# Qwiic_Shield_for_Photon.net
KiCad netlist of a schematic drawn in EAGLE
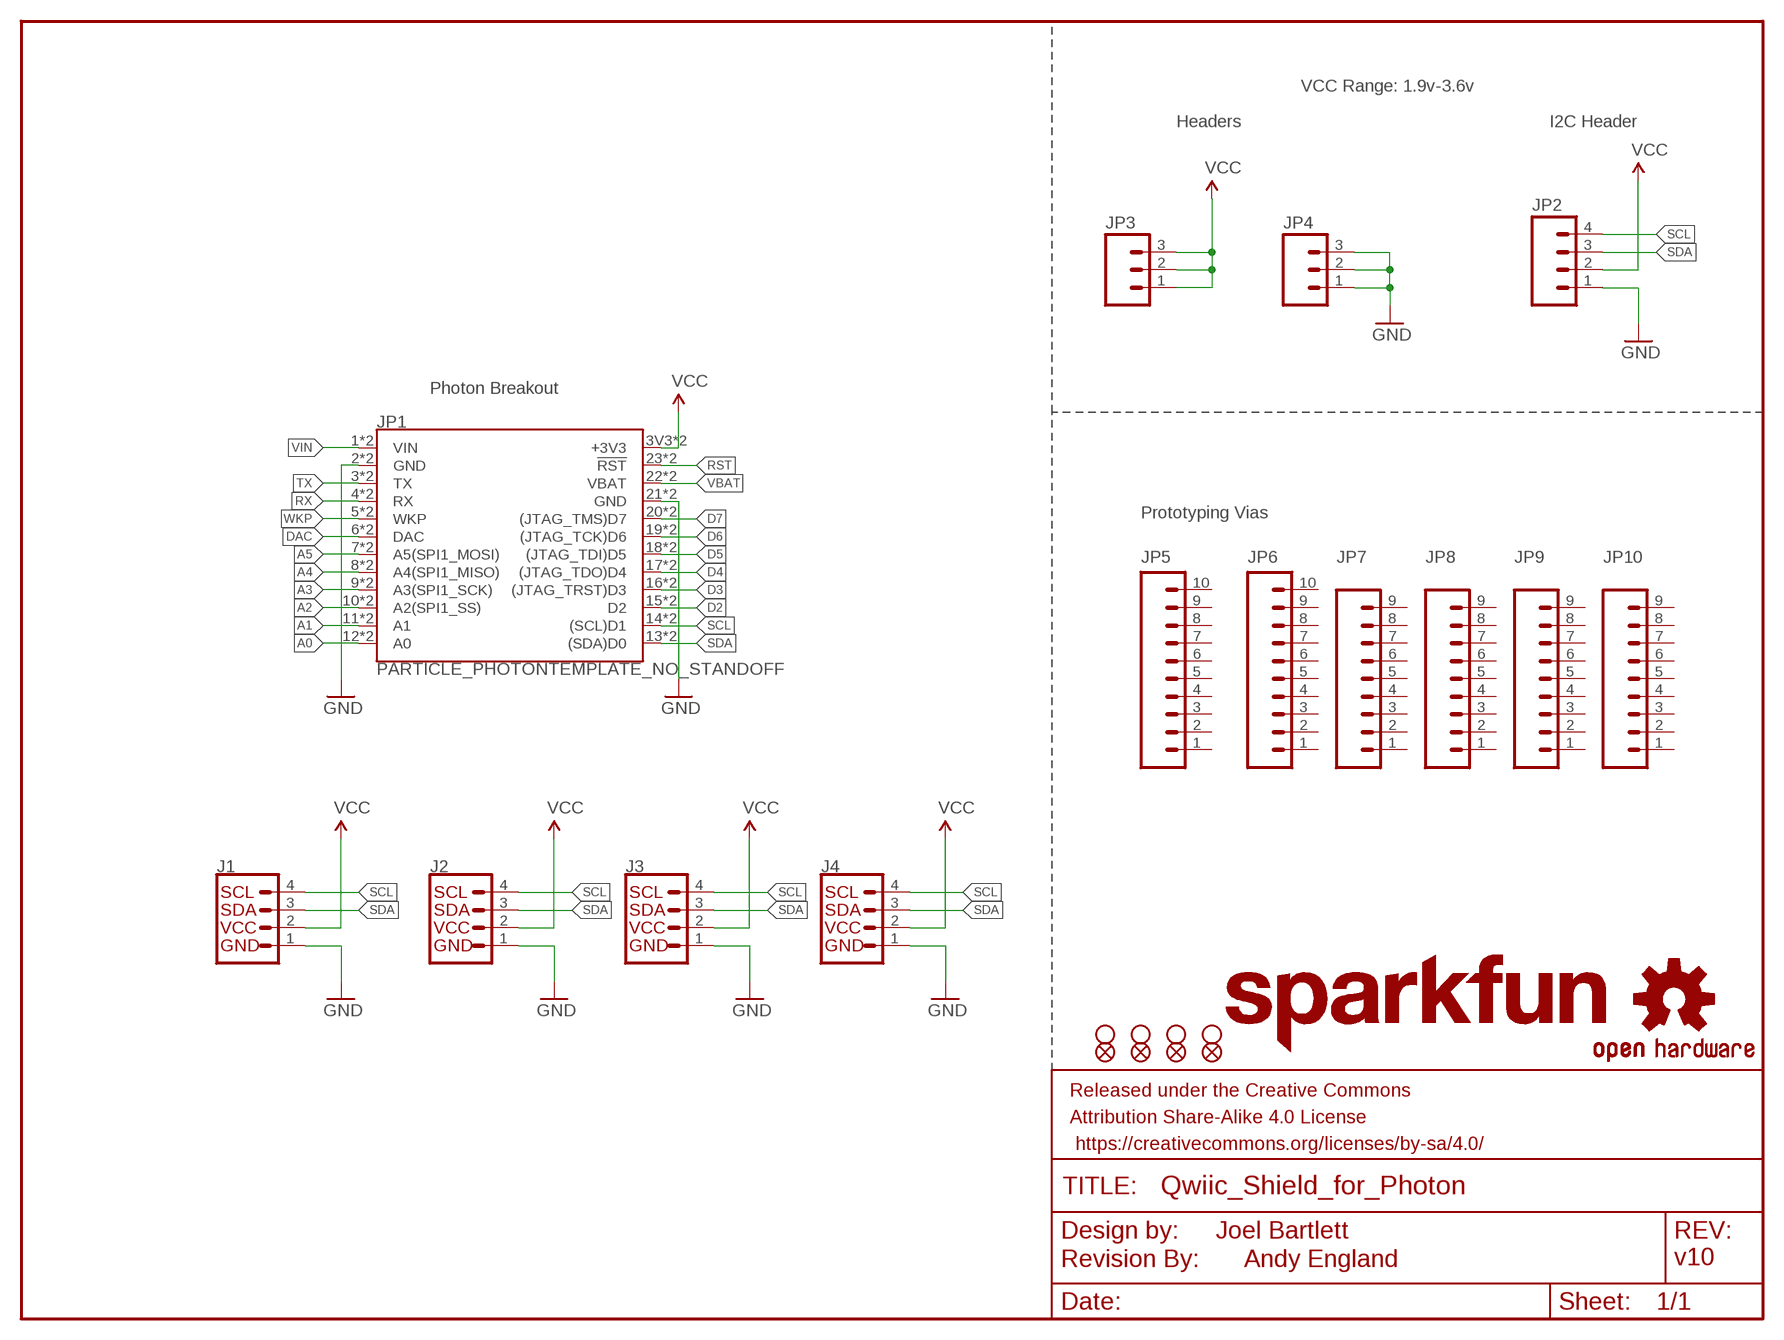
[diagram p0: schematic, sheet 1]

(export (version "E")
  (design (tool "Eeschema 10.0.6"))
  (components
    (comp (ref "FD1")
      (value "FIDUCIALUFIDUCIAL")
      (footprint "eagle-import:FIDUCIAL-MICRO")
      (libsource (lib "eagle-import") (part "FIDUCIALUFIDUCIAL"))
    )
    (comp (ref "FD2")
      (value "FIDUCIALUFIDUCIAL")
      (footprint "eagle-import:FIDUCIAL-MICRO")
      (libsource (lib "eagle-import") (part "FIDUCIALUFIDUCIAL"))
    )
    (comp (ref "FD3")
      (value "FIDUCIALUFIDUCIAL")
      (footprint "eagle-import:FIDUCIAL-MICRO")
      (libsource (lib "eagle-import") (part "FIDUCIALUFIDUCIAL"))
    )
    (comp (ref "FD4")
      (value "FIDUCIALUFIDUCIAL")
      (footprint "eagle-import:FIDUCIAL-MICRO")
      (libsource (lib "eagle-import") (part "FIDUCIALUFIDUCIAL"))
    )
    (comp (ref "FRAME1")
      (value "FRAME-LETTER")
      (footprint "eagle-import:CREATIVE_COMMONS")
      (libsource (lib "eagle-import") (part "FRAME-LETTER"))
    )
    (comp (ref "H1")
      (value "STAND-OFF")
      (footprint "eagle-import:STAND-OFF")
      (libsource (lib "eagle-import") (part "STAND-OFF"))
    )
    (comp (ref "H2")
      (value "STAND-OFF")
      (footprint "eagle-import:STAND-OFF")
      (libsource (lib "eagle-import") (part "STAND-OFF"))
    )
    (comp (ref "H3")
      (value "STAND-OFF")
      (footprint "eagle-import:STAND-OFF")
      (libsource (lib "eagle-import") (part "STAND-OFF"))
    )
    (comp (ref "H4")
      (value "STAND-OFF")
      (footprint "eagle-import:STAND-OFF")
      (libsource (lib "eagle-import") (part "STAND-OFF"))
    )
    (comp (ref "J1")
      (value "QWIIC_CONNECTORJS-1MM")
      (footprint "eagle-import:1X04_1MM_RA")
      (libsource (lib "eagle-import") (part "QWIIC_CONNECTORJS-1MM"))
    )
    (comp (ref "J2")
      (value "QWIIC_CONNECTORJS-1MM")
      (footprint "eagle-import:1X04_1MM_RA")
      (libsource (lib "eagle-import") (part "QWIIC_CONNECTORJS-1MM"))
    )
    (comp (ref "J3")
      (value "QWIIC_CONNECTORJS-1MM")
      (footprint "eagle-import:1X04_1MM_RA")
      (libsource (lib "eagle-import") (part "QWIIC_CONNECTORJS-1MM"))
    )
    (comp (ref "J4")
      (value "I2C_STANDARDJS-1MM")
      (footprint "eagle-import:1X04_1MM_RA")
      (libsource (lib "eagle-import") (part "I2C_STANDARDJS-1MM"))
    )
    (comp (ref "JP1")
      (value "PARTICLE_PHOTONTEMPLATE_NO_STANDOFF")
      (footprint "eagle-import:PARTICLE_PHOTON_TEMPLATE_NO_STANDOFF")
      (libsource (lib "eagle-import") (part "PARTICLE_PHOTONTEMPLATE_NO_STANDOFF"))
    )
    (comp (ref "JP2")
      (value "M04PTH")
      (footprint "eagle-import:1X04")
      (libsource (lib "eagle-import") (part "M04PTH"))
    )
    (comp (ref "JP3")
      (value "M03PTH")
      (footprint "eagle-import:1X03")
      (libsource (lib "eagle-import") (part "M03PTH"))
    )
    (comp (ref "JP4")
      (value "M03PTH")
      (footprint "eagle-import:1X03")
      (libsource (lib "eagle-import") (part "M03PTH"))
    )
    (comp (ref "JP5")
      (value "M10NO_SILK_PTH_FEMALE")
      (footprint "eagle-import:1X10_NO_SILK")
      (libsource (lib "eagle-import") (part "M10NO_SILK_PTH_FEMALE"))
    )
    (comp (ref "JP6")
      (value "M10NO_SILK_PTH_FEMALE")
      (footprint "eagle-import:1X10_NO_SILK")
      (libsource (lib "eagle-import") (part "M10NO_SILK_PTH_FEMALE"))
    )
    (comp (ref "JP7")
      (value "M09NO_SILK")
      (footprint "eagle-import:1X09_NO_SILK")
      (libsource (lib "eagle-import") (part "M09NO_SILK"))
    )
    (comp (ref "JP8")
      (value "M09NO_SILK")
      (footprint "eagle-import:1X09_NO_SILK")
      (libsource (lib "eagle-import") (part "M09NO_SILK"))
    )
    (comp (ref "JP9")
      (value "M09NO_SILK")
      (footprint "eagle-import:1X09_NO_SILK")
      (libsource (lib "eagle-import") (part "M09NO_SILK"))
    )
    (comp (ref "JP10")
      (value "M09NO_SILK")
      (footprint "eagle-import:1X09_NO_SILK")
      (libsource (lib "eagle-import") (part "M09NO_SILK"))
    )
    (comp (ref "LOGO1")
      (value "OSHW-LOGOM")
      (footprint "eagle-import:OSHW-LOGO-M")
      (libsource (lib "eagle-import") (part "OSHW-LOGOM"))
    )
    (comp (ref "LOGO2")
      (value "REVISION")
      (footprint "eagle-import:REVISION")
      (libsource (lib "eagle-import") (part "REVISION"))
    )
    (comp (ref "U$4")
      (value "SFE_LOGO_NAME.1_INCH")
      (footprint "eagle-import:SFE_LOGO_NAME_.1")
      (libsource (lib "eagle-import") (part "SFE_LOGO_NAME.1_INCH"))
    )
  )
  (nets
    (net (code "1") (name "A0") (class "Default")
      (node (ref "JP1") (pin "12") (pinfunction "A0_12") (pintype "bidirectional"))
      (node (ref "JP1") (pin "A0") (pinfunction "A0_A0") (pintype "bidirectional"))
    )
    (net (code "2") (name "A1") (class "Default")
      (node (ref "JP1") (pin "11") (pinfunction "A1_11") (pintype "bidirectional"))
      (node (ref "JP1") (pin "A1") (pinfunction "A1_A1") (pintype "bidirectional"))
    )
    (net (code "3") (name "A2") (class "Default")
      (node (ref "JP1") (pin "10") (pinfunction "A2(SPI1_SS)_10") (pintype "bidirectional"))
      (node (ref "JP1") (pin "A2") (pinfunction "A2(SPI1_SS)_A2") (pintype "bidirectional"))
    )
    (net (code "4") (name "A3") (class "Default")
      (node (ref "JP1") (pin "9") (pinfunction "A3(SPI1_SCK)_9") (pintype "bidirectional"))
      (node (ref "JP1") (pin "A3") (pinfunction "A3(SPI1_SCK)_A3") (pintype "bidirectional"))
    )
    (net (code "5") (name "A4") (class "Default")
      (node (ref "JP1") (pin "8") (pinfunction "A4(SPI1_MISO)_8") (pintype "bidirectional"))
      (node (ref "JP1") (pin "A4") (pinfunction "A4(SPI1_MISO)_A4") (pintype "bidirectional"))
    )
    (net (code "6") (name "A5") (class "Default")
      (node (ref "JP1") (pin "7") (pinfunction "A5(SPI1_MOSI)_7") (pintype "bidirectional"))
      (node (ref "JP1") (pin "A5") (pinfunction "A5(SPI1_MOSI)_A5") (pintype "bidirectional"))
    )
    (net (code "7") (name "D2") (class "Default")
      (node (ref "JP1") (pin "15") (pinfunction "D2_15") (pintype "bidirectional"))
      (node (ref "JP1") (pin "D2") (pinfunction "D2_D2") (pintype "bidirectional"))
    )
    (net (code "8") (name "D3") (class "Default")
      (node (ref "JP1") (pin "16") (pinfunction "(JTAG_TRST)D3_16") (pintype "bidirectional"))
      (node (ref "JP1") (pin "D3") (pinfunction "(JTAG_TRST)D3_D3") (pintype "bidirectional"))
    )
    (net (code "9") (name "D4") (class "Default")
      (node (ref "JP1") (pin "17") (pinfunction "(JTAG_TDO)D4_17") (pintype "bidirectional"))
      (node (ref "JP1") (pin "D4") (pinfunction "(JTAG_TDO)D4_D4") (pintype "bidirectional"))
    )
    (net (code "10") (name "D5") (class "Default")
      (node (ref "JP1") (pin "18") (pinfunction "(JTAG_TDI)D5_18") (pintype "bidirectional"))
      (node (ref "JP1") (pin "D5") (pinfunction "(JTAG_TDI)D5_D5") (pintype "bidirectional"))
    )
    (net (code "11") (name "D6") (class "Default")
      (node (ref "JP1") (pin "19") (pinfunction "(JTAG_TCK)D6_19") (pintype "bidirectional"))
      (node (ref "JP1") (pin "D6") (pinfunction "(JTAG_TCK)D6_D6") (pintype "bidirectional"))
    )
    (net (code "12") (name "D7") (class "Default")
      (node (ref "JP1") (pin "20") (pinfunction "(JTAG_TMS)D7_20") (pintype "bidirectional"))
      (node (ref "JP1") (pin "D7") (pinfunction "(JTAG_TMS)D7_D7") (pintype "bidirectional"))
    )
    (net (code "13") (name "DAC") (class "Default")
      (node (ref "JP1") (pin "6") (pinfunction "DAC_6") (pintype "bidirectional"))
      (node (ref "JP1") (pin "DAC") (pinfunction "DAC_DAC") (pintype "bidirectional"))
    )
    (net (code "14") (name "GND") (class "Default")
      (node (ref "J1") (pin "1") (pinfunction "GND_1") (pintype "power_in"))
      (node (ref "J2") (pin "1") (pinfunction "GND_1") (pintype "power_in"))
      (node (ref "J3") (pin "1") (pinfunction "GND_1") (pintype "power_in"))
      (node (ref "J4") (pin "1") (pinfunction "GND_1") (pintype "power_in"))
      (node (ref "JP1") (pin "2") (pinfunction "GND_2") (pintype "power_in"))
      (node (ref "JP1") (pin "21") (pinfunction "GND_21") (pintype "power_in"))
      (node (ref "JP1") (pin "GND@0") (pinfunction "GND_GND@0") (pintype "power_in"))
      (node (ref "JP1") (pin "GND@2") (pinfunction "GND_GND@2") (pintype "power_in"))
      (node (ref "JP2") (pin "1") (pinfunction "1_1") (pintype "passive"))
      (node (ref "JP4") (pin "1") (pinfunction "1_1") (pintype "passive"))
      (node (ref "JP4") (pin "2") (pinfunction "2_2") (pintype "passive"))
      (node (ref "JP4") (pin "3") (pinfunction "3_3") (pintype "passive"))
    )
    (net (code "15") (name "RST") (class "Default")
      (node (ref "JP1") (pin "23") (pinfunction "~{RST}_23") (pintype "bidirectional"))
      (node (ref "JP1") (pin "RST") (pinfunction "~{RST}_RST") (pintype "bidirectional"))
    )
    (net (code "16") (name "RX") (class "Default")
      (node (ref "JP1") (pin "4") (pinfunction "RX_4") (pintype "bidirectional"))
      (node (ref "JP1") (pin "RX") (pinfunction "RX_RX") (pintype "bidirectional"))
    )
    (net (code "17") (name "SCL") (class "Default")
      (node (ref "J1") (pin "4") (pinfunction "SCL_4") (pintype "passive"))
      (node (ref "J2") (pin "4") (pinfunction "SCL_4") (pintype "passive"))
      (node (ref "J3") (pin "4") (pinfunction "SCL_4") (pintype "passive"))
      (node (ref "J4") (pin "4") (pinfunction "SCL_4") (pintype "passive"))
      (node (ref "JP1") (pin "14") (pinfunction "(SCL)D1_14") (pintype "bidirectional"))
      (node (ref "JP1") (pin "D1") (pinfunction "(SCL)D1_D1") (pintype "bidirectional"))
      (node (ref "JP2") (pin "4") (pinfunction "4_4") (pintype "passive"))
    )
    (net (code "18") (name "SDA") (class "Default")
      (node (ref "J1") (pin "3") (pinfunction "SDA_3") (pintype "passive"))
      (node (ref "J2") (pin "3") (pinfunction "SDA_3") (pintype "passive"))
      (node (ref "J3") (pin "3") (pinfunction "SDA_3") (pintype "passive"))
      (node (ref "J4") (pin "3") (pinfunction "SDA_3") (pintype "passive"))
      (node (ref "JP1") (pin "13") (pinfunction "(SDA)D0_13") (pintype "bidirectional"))
      (node (ref "JP1") (pin "D0") (pinfunction "(SDA)D0_D0") (pintype "bidirectional"))
      (node (ref "JP2") (pin "3") (pinfunction "3_3") (pintype "passive"))
    )
    (net (code "19") (name "TX") (class "Default")
      (node (ref "JP1") (pin "3") (pinfunction "TX_3") (pintype "bidirectional"))
      (node (ref "JP1") (pin "TX") (pinfunction "TX_TX") (pintype "bidirectional"))
    )
    (net (code "20") (name "VBAT") (class "Default")
      (node (ref "JP1") (pin "22") (pinfunction "VBAT_22") (pintype "power_in"))
      (node (ref "JP1") (pin "VBAT") (pinfunction "VBAT_VBAT") (pintype "power_in"))
    )
    (net (code "21") (name "VCC") (class "Default")
      (node (ref "J1") (pin "2") (pinfunction "VCC_2") (pintype "power_in"))
      (node (ref "J2") (pin "2") (pinfunction "VCC_2") (pintype "power_in"))
      (node (ref "J3") (pin "2") (pinfunction "VCC_2") (pintype "power_in"))
      (node (ref "J4") (pin "2") (pinfunction "VCC_2") (pintype "power_in"))
      (node (ref "JP1") (pin "24") (pinfunction "+3V3_24") (pintype "power_in"))
      (node (ref "JP1") (pin "3V3") (pinfunction "+3V3_3V3") (pintype "power_in"))
      (node (ref "JP2") (pin "2") (pinfunction "2_2") (pintype "passive"))
      (node (ref "JP3") (pin "1") (pinfunction "1_1") (pintype "passive"))
      (node (ref "JP3") (pin "2") (pinfunction "2_2") (pintype "passive"))
      (node (ref "JP3") (pin "3") (pinfunction "3_3") (pintype "passive"))
    )
    (net (code "22") (name "VIN") (class "Default")
      (node (ref "JP1") (pin "1") (pinfunction "VIN_1") (pintype "power_in"))
      (node (ref "JP1") (pin "VIN") (pinfunction "VIN_VIN") (pintype "power_in"))
    )
    (net (code "23") (name "WKP") (class "Default")
      (node (ref "JP1") (pin "5") (pinfunction "WKP_5") (pintype "bidirectional"))
      (node (ref "JP1") (pin "WKP") (pinfunction "WKP_WKP") (pintype "bidirectional"))
    )
    (net (code "24") (name "unconnected-(JP5-Pad1)") (class "Default")
      (node (ref "JP5") (pin "1") (pinfunction "1_1") (pintype "passive"))
    )
    (net (code "25") (name "unconnected-(JP5-Pad2)") (class "Default")
      (node (ref "JP5") (pin "2") (pinfunction "2_2") (pintype "passive"))
    )
    (net (code "26") (name "unconnected-(JP5-Pad3)") (class "Default")
      (node (ref "JP5") (pin "3") (pinfunction "3_3") (pintype "passive"))
    )
    (net (code "27") (name "unconnected-(JP5-Pad4)") (class "Default")
      (node (ref "JP5") (pin "4") (pinfunction "4_4") (pintype "passive"))
    )
    (net (code "28") (name "unconnected-(JP5-Pad5)") (class "Default")
      (node (ref "JP5") (pin "5") (pinfunction "5_5") (pintype "passive"))
    )
    (net (code "29") (name "unconnected-(JP5-Pad6)") (class "Default")
      (node (ref "JP5") (pin "6") (pinfunction "6_6") (pintype "passive"))
    )
    (net (code "30") (name "unconnected-(JP5-Pad7)") (class "Default")
      (node (ref "JP5") (pin "7") (pinfunction "7_7") (pintype "passive"))
    )
    (net (code "31") (name "unconnected-(JP5-Pad8)") (class "Default")
      (node (ref "JP5") (pin "8") (pinfunction "8_8") (pintype "passive"))
    )
    (net (code "32") (name "unconnected-(JP5-Pad9)") (class "Default")
      (node (ref "JP5") (pin "9") (pinfunction "9_9") (pintype "passive"))
    )
    (net (code "33") (name "unconnected-(JP5-Pad10)") (class "Default")
      (node (ref "JP5") (pin "10") (pinfunction "10_10") (pintype "passive"))
    )
    (net (code "34") (name "unconnected-(JP6-Pad1)") (class "Default")
      (node (ref "JP6") (pin "1") (pinfunction "1_1") (pintype "passive"))
    )
    (net (code "35") (name "unconnected-(JP6-Pad2)") (class "Default")
      (node (ref "JP6") (pin "2") (pinfunction "2_2") (pintype "passive"))
    )
    (net (code "36") (name "unconnected-(JP6-Pad3)") (class "Default")
      (node (ref "JP6") (pin "3") (pinfunction "3_3") (pintype "passive"))
    )
    (net (code "37") (name "unconnected-(JP6-Pad4)") (class "Default")
      (node (ref "JP6") (pin "4") (pinfunction "4_4") (pintype "passive"))
    )
    (net (code "38") (name "unconnected-(JP6-Pad5)") (class "Default")
      (node (ref "JP6") (pin "5") (pinfunction "5_5") (pintype "passive"))
    )
    (net (code "39") (name "unconnected-(JP6-Pad6)") (class "Default")
      (node (ref "JP6") (pin "6") (pinfunction "6_6") (pintype "passive"))
    )
    (net (code "40") (name "unconnected-(JP6-Pad7)") (class "Default")
      (node (ref "JP6") (pin "7") (pinfunction "7_7") (pintype "passive"))
    )
    (net (code "41") (name "unconnected-(JP6-Pad8)") (class "Default")
      (node (ref "JP6") (pin "8") (pinfunction "8_8") (pintype "passive"))
    )
    (net (code "42") (name "unconnected-(JP6-Pad9)") (class "Default")
      (node (ref "JP6") (pin "9") (pinfunction "9_9") (pintype "passive"))
    )
    (net (code "43") (name "unconnected-(JP6-Pad10)") (class "Default")
      (node (ref "JP6") (pin "10") (pinfunction "10_10") (pintype "passive"))
    )
    (net (code "44") (name "unconnected-(JP7-Pad1)") (class "Default")
      (node (ref "JP7") (pin "1") (pinfunction "1_1") (pintype "passive"))
    )
    (net (code "45") (name "unconnected-(JP7-Pad2)") (class "Default")
      (node (ref "JP7") (pin "2") (pinfunction "2_2") (pintype "passive"))
    )
    (net (code "46") (name "unconnected-(JP7-Pad3)") (class "Default")
      (node (ref "JP7") (pin "3") (pinfunction "3_3") (pintype "passive"))
    )
    (net (code "47") (name "unconnected-(JP7-Pad4)") (class "Default")
      (node (ref "JP7") (pin "4") (pinfunction "4_4") (pintype "passive"))
    )
    (net (code "48") (name "unconnected-(JP7-Pad5)") (class "Default")
      (node (ref "JP7") (pin "5") (pinfunction "5_5") (pintype "passive"))
    )
    (net (code "49") (name "unconnected-(JP7-Pad6)") (class "Default")
      (node (ref "JP7") (pin "6") (pinfunction "6_6") (pintype "passive"))
    )
    (net (code "50") (name "unconnected-(JP7-Pad7)") (class "Default")
      (node (ref "JP7") (pin "7") (pinfunction "7_7") (pintype "passive"))
    )
    (net (code "51") (name "unconnected-(JP7-Pad8)") (class "Default")
      (node (ref "JP7") (pin "8") (pinfunction "8_8") (pintype "passive"))
    )
    (net (code "52") (name "unconnected-(JP7-Pad9)") (class "Default")
      (node (ref "JP7") (pin "9") (pinfunction "9_9") (pintype "passive"))
    )
    (net (code "53") (name "unconnected-(JP8-Pad1)") (class "Default")
      (node (ref "JP8") (pin "1") (pinfunction "1_1") (pintype "passive"))
    )
    (net (code "54") (name "unconnected-(JP8-Pad2)") (class "Default")
      (node (ref "JP8") (pin "2") (pinfunction "2_2") (pintype "passive"))
    )
    (net (code "55") (name "unconnected-(JP8-Pad3)") (class "Default")
      (node (ref "JP8") (pin "3") (pinfunction "3_3") (pintype "passive"))
    )
    (net (code "56") (name "unconnected-(JP8-Pad4)") (class "Default")
      (node (ref "JP8") (pin "4") (pinfunction "4_4") (pintype "passive"))
    )
    (net (code "57") (name "unconnected-(JP8-Pad5)") (class "Default")
      (node (ref "JP8") (pin "5") (pinfunction "5_5") (pintype "passive"))
    )
    (net (code "58") (name "unconnected-(JP8-Pad6)") (class "Default")
      (node (ref "JP8") (pin "6") (pinfunction "6_6") (pintype "passive"))
    )
    (net (code "59") (name "unconnected-(JP8-Pad7)") (class "Default")
      (node (ref "JP8") (pin "7") (pinfunction "7_7") (pintype "passive"))
    )
    (net (code "60") (name "unconnected-(JP8-Pad8)") (class "Default")
      (node (ref "JP8") (pin "8") (pinfunction "8_8") (pintype "passive"))
    )
    (net (code "61") (name "unconnected-(JP8-Pad9)") (class "Default")
      (node (ref "JP8") (pin "9") (pinfunction "9_9") (pintype "passive"))
    )
    (net (code "62") (name "unconnected-(JP9-Pad1)") (class "Default")
      (node (ref "JP9") (pin "1") (pinfunction "1_1") (pintype "passive"))
    )
    (net (code "63") (name "unconnected-(JP9-Pad2)") (class "Default")
      (node (ref "JP9") (pin "2") (pinfunction "2_2") (pintype "passive"))
    )
    (net (code "64") (name "unconnected-(JP9-Pad3)") (class "Default")
      (node (ref "JP9") (pin "3") (pinfunction "3_3") (pintype "passive"))
    )
    (net (code "65") (name "unconnected-(JP9-Pad4)") (class "Default")
      (node (ref "JP9") (pin "4") (pinfunction "4_4") (pintype "passive"))
    )
    (net (code "66") (name "unconnected-(JP9-Pad5)") (class "Default")
      (node (ref "JP9") (pin "5") (pinfunction "5_5") (pintype "passive"))
    )
    (net (code "67") (name "unconnected-(JP9-Pad6)") (class "Default")
      (node (ref "JP9") (pin "6") (pinfunction "6_6") (pintype "passive"))
    )
    (net (code "68") (name "unconnected-(JP9-Pad7)") (class "Default")
      (node (ref "JP9") (pin "7") (pinfunction "7_7") (pintype "passive"))
    )
    (net (code "69") (name "unconnected-(JP9-Pad8)") (class "Default")
      (node (ref "JP9") (pin "8") (pinfunction "8_8") (pintype "passive"))
    )
    (net (code "70") (name "unconnected-(JP9-Pad9)") (class "Default")
      (node (ref "JP9") (pin "9") (pinfunction "9_9") (pintype "passive"))
    )
    (net (code "71") (name "unconnected-(JP10-Pad1)") (class "Default")
      (node (ref "JP10") (pin "1") (pinfunction "1_1") (pintype "passive"))
    )
    (net (code "72") (name "unconnected-(JP10-Pad2)") (class "Default")
      (node (ref "JP10") (pin "2") (pinfunction "2_2") (pintype "passive"))
    )
    (net (code "73") (name "unconnected-(JP10-Pad3)") (class "Default")
      (node (ref "JP10") (pin "3") (pinfunction "3_3") (pintype "passive"))
    )
    (net (code "74") (name "unconnected-(JP10-Pad4)") (class "Default")
      (node (ref "JP10") (pin "4") (pinfunction "4_4") (pintype "passive"))
    )
    (net (code "75") (name "unconnected-(JP10-Pad5)") (class "Default")
      (node (ref "JP10") (pin "5") (pinfunction "5_5") (pintype "passive"))
    )
    (net (code "76") (name "unconnected-(JP10-Pad6)") (class "Default")
      (node (ref "JP10") (pin "6") (pinfunction "6_6") (pintype "passive"))
    )
    (net (code "77") (name "unconnected-(JP10-Pad7)") (class "Default")
      (node (ref "JP10") (pin "7") (pinfunction "7_7") (pintype "passive"))
    )
    (net (code "78") (name "unconnected-(JP10-Pad8)") (class "Default")
      (node (ref "JP10") (pin "8") (pinfunction "8_8") (pintype "passive"))
    )
    (net (code "79") (name "unconnected-(JP10-Pad9)") (class "Default")
      (node (ref "JP10") (pin "9") (pinfunction "9_9") (pintype "passive"))
    )
  )
)
